# OPT101.net
KiCad netlist of a schematic drawn in EAGLE
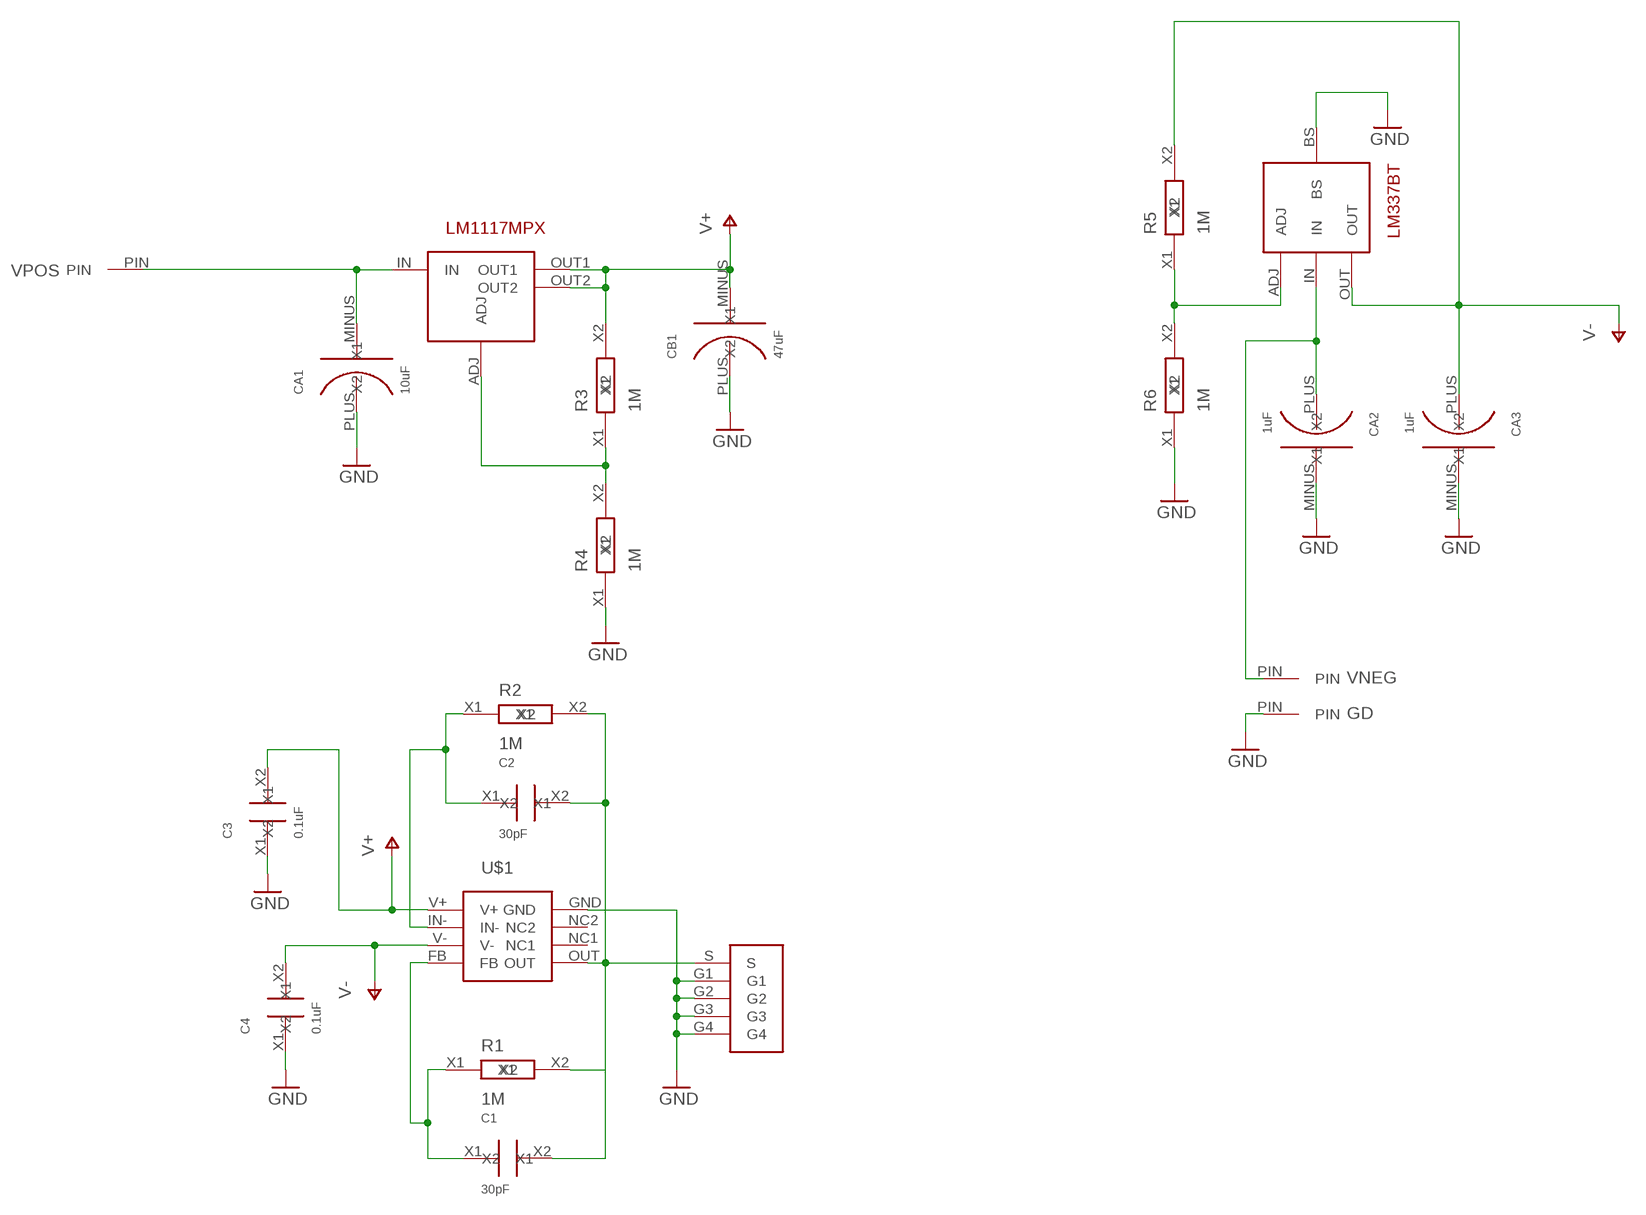
[diagram p0: schematic, sheet 1]

(export (version "E")
  (design (tool "Eeschema 10.0.6"))
  (components
    (comp (ref "C1")
      (value "30pF")
      (footprint "eagle-import:SMD_2.1X1.25")
      (libsource (lib "eagle-import") (part "C_SMD_2.1X1.25"))
    )
    (comp (ref "C2")
      (value "30pF")
      (footprint "eagle-import:SMD_2.1X1.25")
      (libsource (lib "eagle-import") (part "C_SMD_2.1X1.25"))
    )
    (comp (ref "C3")
      (value "0.1uF")
      (footprint "eagle-import:SMD_2.1X1.25")
      (libsource (lib "eagle-import") (part "C_SMD_2.1X1.25"))
    )
    (comp (ref "C4")
      (value "0.1uF")
      (footprint "eagle-import:SMD_2.1X1.25")
      (libsource (lib "eagle-import") (part "C_SMD_2.1X1.25"))
    )
    (comp (ref "CA1")
      (value "10uF")
      (footprint "eagle-import:C_SMD_TA_A")
      (libsource (lib "eagle-import") (part "C_SMD_TA_A"))
    )
    (comp (ref "CA2")
      (value "1uF")
      (footprint "eagle-import:C_SMD_TA_A")
      (libsource (lib "eagle-import") (part "C_SMD_TA_A"))
    )
    (comp (ref "CA3")
      (value "1uF")
      (footprint "eagle-import:C_SMD_TA_A")
      (libsource (lib "eagle-import") (part "C_SMD_TA_A"))
    )
    (comp (ref "CB1")
      (value "47uF")
      (footprint "eagle-import:C_SMD_TA_B")
      (libsource (lib "eagle-import") (part "C_SMD_TA_B"))
    )
    (comp (ref "GD")
      (value "PIN")
      (footprint "eagle-import:PIN")
      (libsource (lib "eagle-import") (part "PIN"))
    )
    (comp (ref "R1")
      (value "1M")
      (footprint "eagle-import:SMD_2.1X1.25")
      (libsource (lib "eagle-import") (part "R_SMD_2.1X1.25"))
    )
    (comp (ref "R2")
      (value "1M")
      (footprint "eagle-import:SMD_2.1X1.25")
      (libsource (lib "eagle-import") (part "R_SMD_2.1X1.25"))
    )
    (comp (ref "R3")
      (value "1M")
      (footprint "eagle-import:SMD_2.1X1.25")
      (libsource (lib "eagle-import") (part "R_SMD_2.1X1.25"))
    )
    (comp (ref "R4")
      (value "1M")
      (footprint "eagle-import:SMD_2.1X1.25")
      (libsource (lib "eagle-import") (part "R_SMD_2.1X1.25"))
    )
    (comp (ref "R5")
      (value "1M")
      (footprint "eagle-import:SMD_2.1X1.25")
      (libsource (lib "eagle-import") (part "R_SMD_2.1X1.25"))
    )
    (comp (ref "R6")
      (value "1M")
      (footprint "eagle-import:SMD_2.1X1.25")
      (libsource (lib "eagle-import") (part "R_SMD_2.1X1.25"))
    )
    (comp (ref "U$1")
      (value "OPT101")
      (footprint "eagle-import:OPT101")
      (libsource (lib "eagle-import") (part "OPT101"))
    )
    (comp (ref "U$2")
      (value "SMA_AN")
      (footprint "eagle-import:SMA_AN")
      (libsource (lib "eagle-import") (part "SMA_AN"))
    )
    (comp (ref "U$3")
      (value "LM1117MPX-ADJ")
      (footprint "eagle-import:LM1117MPX-ADJ")
      (libsource (lib "eagle-import") (part "LM1117MPX-ADJ"))
    )
    (comp (ref "U$4")
      (value "LM337BT")
      (footprint "eagle-import:LM337BT")
      (libsource (lib "eagle-import") (part "LM337BT"))
    )
    (comp (ref "VNEG")
      (value "PIN")
      (footprint "eagle-import:PIN")
      (libsource (lib "eagle-import") (part "PIN"))
    )
    (comp (ref "VPOS")
      (value "PIN")
      (footprint "eagle-import:PIN")
      (libsource (lib "eagle-import") (part "PIN"))
    )
  )
  (nets
    (net (code "1") (name "GND") (class "Default")
      (node (ref "C3") (pin "X1") (pinfunction "X1_X1") (pintype "bidirectional"))
      (node (ref "C4") (pin "X1") (pinfunction "X1_X1") (pintype "bidirectional"))
      (node (ref "CA1") (pin "PLUS") (pinfunction "X1_PLUS") (pintype "bidirectional"))
      (node (ref "CA2") (pin "MINUS") (pinfunction "X2_MINUS") (pintype "bidirectional"))
      (node (ref "CA3") (pin "MINUS") (pinfunction "X2_MINUS") (pintype "bidirectional"))
      (node (ref "CB1") (pin "PLUS") (pinfunction "X1_PLUS") (pintype "bidirectional"))
      (node (ref "GD") (pin "PIN") (pinfunction "PIN_PIN") (pintype "bidirectional"))
      (node (ref "R4") (pin "X1") (pinfunction "X1_X1") (pintype "bidirectional"))
      (node (ref "R6") (pin "X1") (pinfunction "X1_X1") (pintype "bidirectional"))
      (node (ref "U$1") (pin "GND") (pinfunction "GND_GND") (pintype "bidirectional"))
      (node (ref "U$2") (pin "G1") (pinfunction "G1_G1") (pintype "bidirectional"))
      (node (ref "U$2") (pin "G2") (pinfunction "G2_G2") (pintype "bidirectional"))
      (node (ref "U$2") (pin "G3") (pinfunction "G3_G3") (pintype "bidirectional"))
      (node (ref "U$2") (pin "G4") (pinfunction "G4_G4") (pintype "bidirectional"))
      (node (ref "U$4") (pin "BS") (pinfunction "BS_BS") (pintype "bidirectional"))
    )
    (net (code "2") (name "Net-(C1-PadX1)") (class "Default")
      (node (ref "C1") (pin "X1") (pinfunction "X1_X1") (pintype "bidirectional"))
      (node (ref "R1") (pin "X1") (pinfunction "X1_X1") (pintype "bidirectional"))
      (node (ref "U$1") (pin "FB") (pinfunction "FB_FB") (pintype "bidirectional"))
    )
    (net (code "3") (name "Net-(C1-PadX2)") (class "Default")
      (node (ref "C1") (pin "X2") (pinfunction "X2_X2") (pintype "bidirectional"))
      (node (ref "C2") (pin "X2") (pinfunction "X2_X2") (pintype "bidirectional"))
      (node (ref "R1") (pin "X2") (pinfunction "X2_X2") (pintype "bidirectional"))
      (node (ref "R2") (pin "X2") (pinfunction "X2_X2") (pintype "bidirectional"))
      (node (ref "U$1") (pin "OUT") (pinfunction "OUT_OUT") (pintype "bidirectional"))
      (node (ref "U$2") (pin "S") (pinfunction "S_S") (pintype "bidirectional"))
    )
    (net (code "4") (name "Net-(C2-PadX1)") (class "Default")
      (node (ref "C2") (pin "X1") (pinfunction "X1_X1") (pintype "bidirectional"))
      (node (ref "R2") (pin "X1") (pinfunction "X1_X1") (pintype "bidirectional"))
      (node (ref "U$1") (pin "IN-") (pinfunction "IN-_IN-") (pintype "bidirectional"))
    )
    (net (code "5") (name "Net-(CA1-X2)") (class "Default")
      (node (ref "CA1") (pin "MINUS") (pinfunction "X2_MINUS") (pintype "bidirectional"))
      (node (ref "U$3") (pin "IN") (pinfunction "IN_IN") (pintype "bidirectional"))
      (node (ref "VPOS") (pin "PIN") (pinfunction "PIN_PIN") (pintype "bidirectional"))
    )
    (net (code "6") (name "Net-(CA2-X1)") (class "Default")
      (node (ref "CA2") (pin "PLUS") (pinfunction "X1_PLUS") (pintype "bidirectional"))
      (node (ref "U$4") (pin "IN") (pinfunction "IN_IN") (pintype "bidirectional"))
      (node (ref "VNEG") (pin "PIN") (pinfunction "PIN_PIN") (pintype "bidirectional"))
    )
    (net (code "7") (name "Net-(R3-PadX1)") (class "Default")
      (node (ref "R3") (pin "X1") (pinfunction "X1_X1") (pintype "bidirectional"))
      (node (ref "R4") (pin "X2") (pinfunction "X2_X2") (pintype "bidirectional"))
      (node (ref "U$3") (pin "ADJ") (pinfunction "ADJ_ADJ") (pintype "bidirectional"))
    )
    (net (code "8") (name "Net-(R5-PadX1)") (class "Default")
      (node (ref "R5") (pin "X1") (pinfunction "X1_X1") (pintype "bidirectional"))
      (node (ref "R6") (pin "X2") (pinfunction "X2_X2") (pintype "bidirectional"))
      (node (ref "U$4") (pin "ADJ") (pinfunction "ADJ_ADJ") (pintype "bidirectional"))
    )
    (net (code "9") (name "V+") (class "Default")
      (node (ref "C3") (pin "X2") (pinfunction "X2_X2") (pintype "bidirectional"))
      (node (ref "CB1") (pin "MINUS") (pinfunction "X2_MINUS") (pintype "bidirectional"))
      (node (ref "R3") (pin "X2") (pinfunction "X2_X2") (pintype "bidirectional"))
      (node (ref "U$1") (pin "V+") (pinfunction "V+_V+") (pintype "bidirectional"))
      (node (ref "U$3") (pin "OUT1") (pinfunction "OUT1_OUT1") (pintype "bidirectional"))
      (node (ref "U$3") (pin "OUT2") (pinfunction "OUT2_OUT2") (pintype "bidirectional"))
    )
    (net (code "10") (name "V-") (class "Default")
      (node (ref "C4") (pin "X2") (pinfunction "X2_X2") (pintype "bidirectional"))
      (node (ref "CA3") (pin "PLUS") (pinfunction "X1_PLUS") (pintype "bidirectional"))
      (node (ref "R5") (pin "X2") (pinfunction "X2_X2") (pintype "bidirectional"))
      (node (ref "U$1") (pin "V-") (pinfunction "V-_V-") (pintype "bidirectional"))
      (node (ref "U$4") (pin "OUT") (pinfunction "OUT_OUT") (pintype "bidirectional"))
    )
    (net (code "11") (name "unconnected-(U$1-PadNC1)") (class "Default")
      (node (ref "U$1") (pin "NC1") (pinfunction "NC1_NC1") (pintype "bidirectional"))
    )
    (net (code "12") (name "unconnected-(U$1-PadNC2)") (class "Default")
      (node (ref "U$1") (pin "NC2") (pinfunction "NC2_NC2") (pintype "bidirectional"))
    )
  )
)
